# Sedna_Power_Board_v3.net
KiCad netlist of a schematic drawn in EAGLE
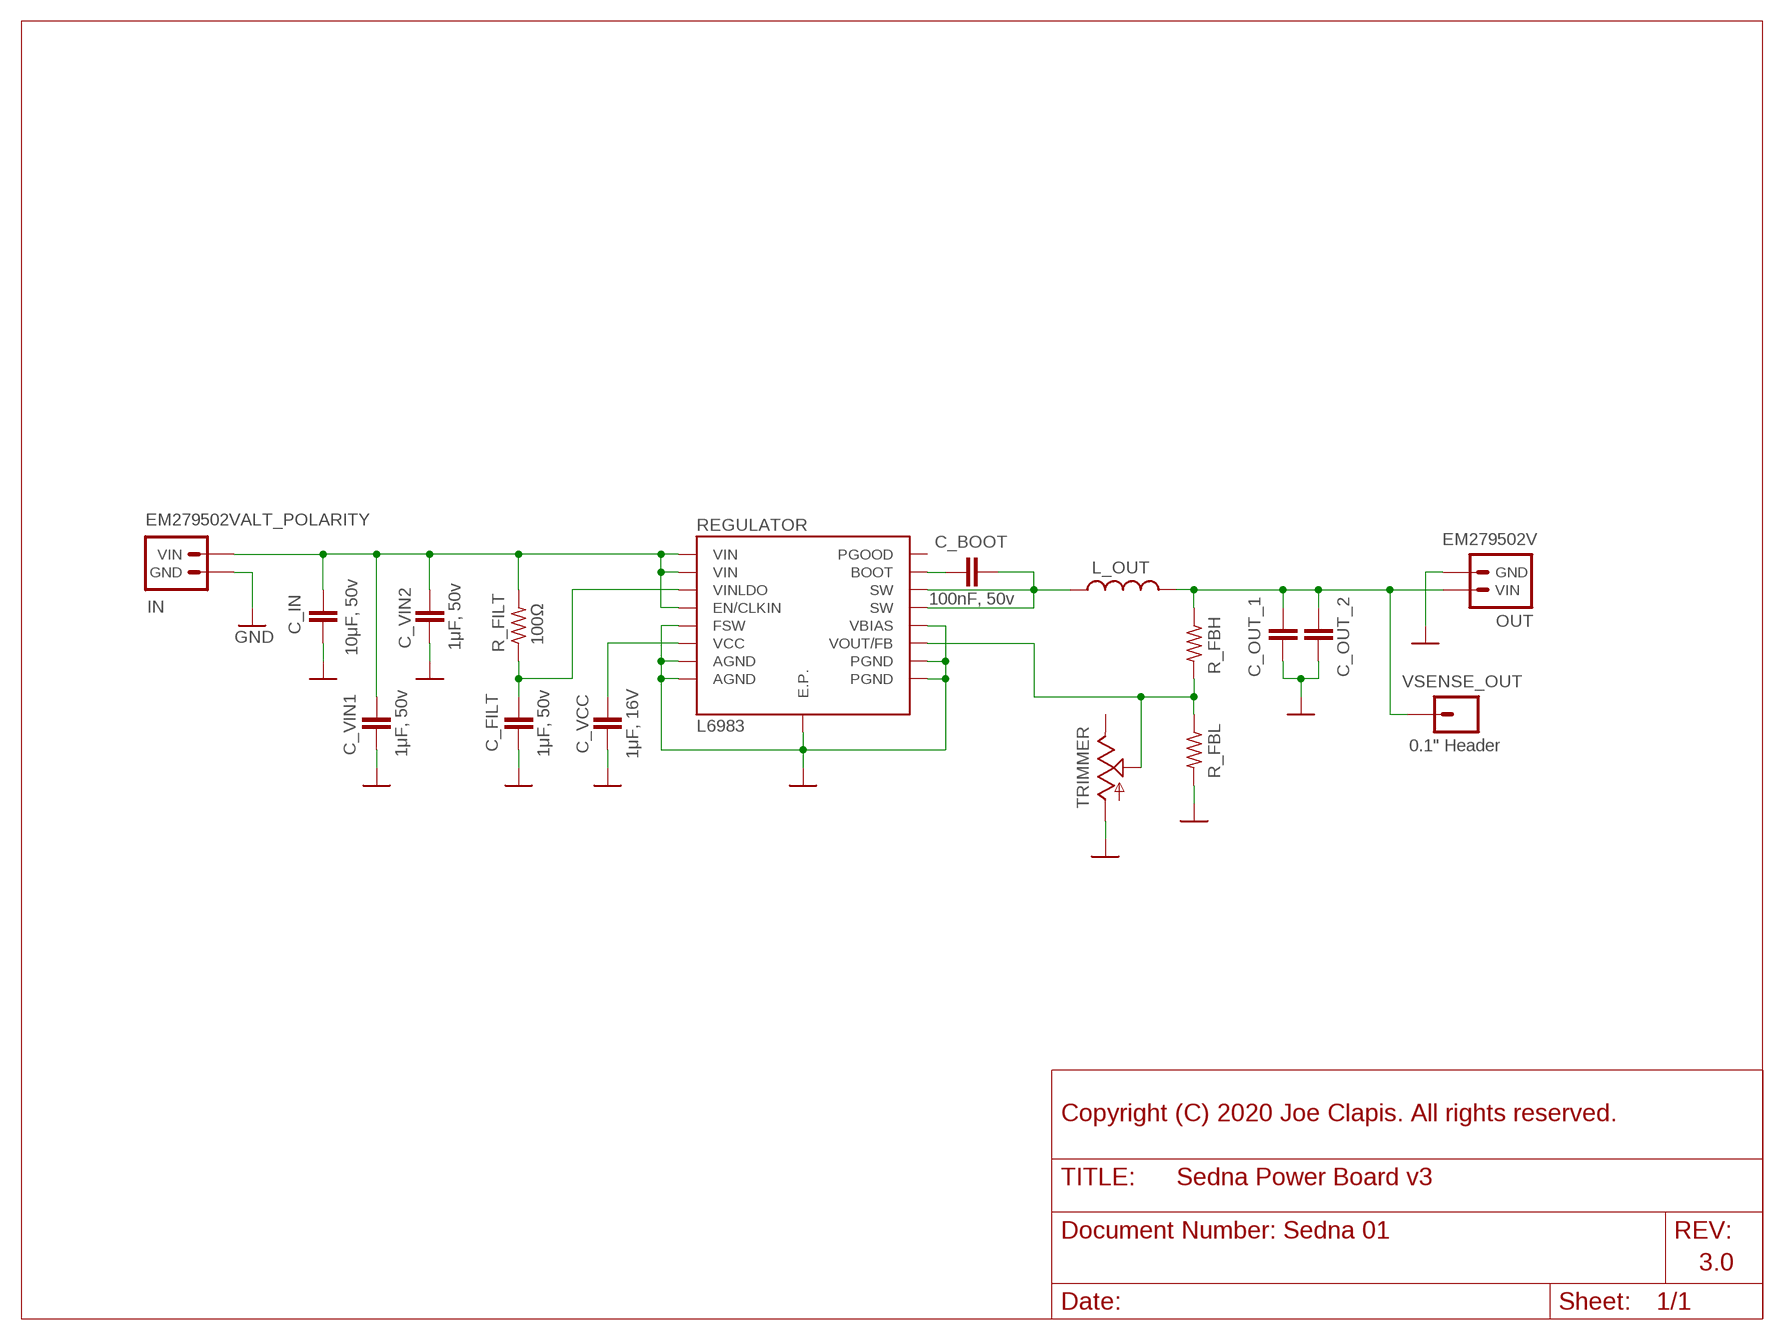
[diagram p0: schematic, sheet 1]

(export (version "E")
  (design (tool "Eeschema 10.0.6"))
  (components
    (comp (ref "C_BOOT")
      (value "100nF, 50v")
      (footprint "eagle-import:C0805")
      (libsource (lib "eagle-import") (part "C-EUC0805"))
    )
    (comp (ref "C_FILT")
      (value "1μF, 50v")
      (footprint "eagle-import:C0805")
      (libsource (lib "eagle-import") (part "C-EUC0805"))
    )
    (comp (ref "C_IN")
      (value "10μF, 50v")
      (footprint "eagle-import:C1206")
      (libsource (lib "eagle-import") (part "C-EUC1206"))
    )
    (comp (ref "C_OUT_1")
      (value "TDK_C2220_5750")
      (footprint "eagle-import:TDK_C2220_5750")
      (libsource (lib "eagle-import") (part "TDK_C2220_5750"))
    )
    (comp (ref "C_OUT_2")
      (value "TDK_C2220_5750")
      (footprint "eagle-import:TDK_C2220_5750")
      (libsource (lib "eagle-import") (part "TDK_C2220_5750"))
    )
    (comp (ref "C_VCC")
      (value "1μF, 16V")
      (footprint "eagle-import:C0805")
      (libsource (lib "eagle-import") (part "C-EUC0805"))
    )
    (comp (ref "C_VIN1")
      (value "1μF, 50v")
      (footprint "eagle-import:C0805")
      (libsource (lib "eagle-import") (part "C-EUC0805"))
    )
    (comp (ref "C_VIN2")
      (value "1μF, 50v")
      (footprint "eagle-import:C0805")
      (libsource (lib "eagle-import") (part "C-EUC0805"))
    )
    (comp (ref "IN")
      (value "EM279502VALT_POLARITY")
      (footprint "eagle-import:EM279502V")
      (libsource (lib "eagle-import") (part "EM279502VALT_POLARITY"))
    )
    (comp (ref "L_OUT")
      (value "PA4343_FP2")
      (footprint "eagle-import:PA4343_FP2")
      (libsource (lib "eagle-import") (part "PA4343_FP2"))
    )
    (comp (ref "OUT")
      (value "EM279502V")
      (footprint "eagle-import:EM279502V")
      (libsource (lib "eagle-import") (part "EM279502V"))
    )
    (comp (ref "REGULATOR")
      (value "L6983")
      (footprint "eagle-import:L6983")
      (fields (field (name "SPICEPREFIX") "X"))
      (libsource (lib "eagle-import") (part "L6983"))
    )
    (comp (ref "R_FBH")
      (value "R-US_R0805")
      (footprint "eagle-import:R0805")
      (libsource (lib "eagle-import") (part "R-US_R0805"))
    )
    (comp (ref "R_FBL")
      (value "R-US_R0805")
      (footprint "eagle-import:R0805")
      (libsource (lib "eagle-import") (part "R-US_R0805"))
    )
    (comp (ref "R_FILT")
      (value "100Ω")
      (footprint "eagle-import:R0805")
      (libsource (lib "eagle-import") (part "R-US_R0805"))
    )
    (comp (ref "TRIMMER")
      (value "BOURNS_3361S")
      (footprint "eagle-import:BOURNS_3361S")
      (libsource (lib "eagle-import") (part "BOURNS_3361S"))
    )
    (comp (ref "VSENSE_OUT")
      (value "0.1\" Header")
      (footprint "eagle-import:1X01")
      (libsource (lib "eagle-import") (part "M01PTH"))
    )
  )
  (nets
    (net (code "1") (name "GND") (class "Default")
      (node (ref "C_FILT") (pin "2") (pinfunction "2_2") (pintype "passive"))
      (node (ref "C_IN") (pin "2") (pinfunction "2_2") (pintype "passive"))
      (node (ref "C_OUT_1") (pin "2") (pinfunction "2_2") (pintype "passive"))
      (node (ref "C_OUT_2") (pin "2") (pinfunction "2_2") (pintype "passive"))
      (node (ref "C_VCC") (pin "2") (pinfunction "2_2") (pintype "passive"))
      (node (ref "C_VIN1") (pin "2") (pinfunction "2_2") (pintype "passive"))
      (node (ref "C_VIN2") (pin "2") (pinfunction "2_2") (pintype "passive"))
      (node (ref "IN") (pin "1A") (pinfunction "GND_1A") (pintype "passive"))
      (node (ref "IN") (pin "1B") (pinfunction "GND_1B") (pintype "passive"))
      (node (ref "OUT") (pin "2A") (pinfunction "GND_2A") (pintype "passive"))
      (node (ref "OUT") (pin "2B") (pinfunction "GND_2B") (pintype "passive"))
      (node (ref "REGULATOR") (pin "10_AGND") (pinfunction "AGND_10_AGND") (pintype "power_in"))
      (node (ref "REGULATOR") (pin "13_PGND") (pinfunction "PGND_13_PGND") (pintype "power_in"))
      (node (ref "REGULATOR") (pin "16_PGND") (pinfunction "PGND_16_PGND") (pintype "power_in"))
      (node (ref "REGULATOR") (pin "3_AGND") (pinfunction "AGND_3_AGND") (pintype "power_in"))
      (node (ref "REGULATOR") (pin "6_VBIAS") (pinfunction "VBIAS_6_VBIAS") (pintype "input"))
      (node (ref "REGULATOR") (pin "8_FSW") (pinfunction "FSW_8_FSW") (pintype "output"))
      (node (ref "REGULATOR") (pin "E.P.") (pinfunction "E.P._E.P.") (pintype "power_in"))
      (node (ref "R_FBL") (pin "2") (pinfunction "2_2") (pintype "passive"))
      (node (ref "TRIMMER") (pin "1") (pinfunction "A_1") (pintype "passive"))
    )
    (net (code "2") (name "Net-(C_BOOT-Pad2)") (class "Default")
      (node (ref "C_BOOT") (pin "2") (pinfunction "2_2") (pintype "passive"))
      (node (ref "L_OUT") (pin "1") (pinfunction "1_1") (pintype "passive"))
      (node (ref "REGULATOR") (pin "14_SW") (pinfunction "SW_14_SW") (pintype "power_in"))
      (node (ref "REGULATOR") (pin "15_SW") (pinfunction "SW_15_SW") (pintype "power_in"))
    )
    (net (code "3") (name "Net-(C_OUT_1-Pad1)") (class "Default")
      (node (ref "C_OUT_1") (pin "1") (pinfunction "1_1") (pintype "passive"))
      (node (ref "C_OUT_2") (pin "1") (pinfunction "1_1") (pintype "passive"))
      (node (ref "L_OUT") (pin "2") (pinfunction "2_2") (pintype "passive"))
      (node (ref "OUT") (pin "1A") (pinfunction "VIN_1A") (pintype "passive"))
      (node (ref "OUT") (pin "1B") (pinfunction "VIN_1B") (pintype "passive"))
      (node (ref "R_FBH") (pin "1") (pinfunction "1_1") (pintype "passive"))
      (node (ref "VSENSE_OUT") (pin "1") (pinfunction "1_1") (pintype "passive"))
    )
    (net (code "4") (name "Net-(REGULATOR-BOOT)") (class "Default")
      (node (ref "C_BOOT") (pin "1") (pinfunction "1_1") (pintype "passive"))
      (node (ref "REGULATOR") (pin "11_BOOT") (pinfunction "BOOT_11_BOOT") (pintype "power_in"))
    )
    (net (code "5") (name "Net-(REGULATOR-EN{slash}CLKIN)") (class "Default")
      (node (ref "C_IN") (pin "1") (pinfunction "1_1") (pintype "passive"))
      (node (ref "C_VIN1") (pin "1") (pinfunction "1_1") (pintype "passive"))
      (node (ref "C_VIN2") (pin "1") (pinfunction "1_1") (pintype "passive"))
      (node (ref "IN") (pin "2A") (pinfunction "VIN_2A") (pintype "passive"))
      (node (ref "IN") (pin "2B") (pinfunction "VIN_2B") (pintype "passive"))
      (node (ref "REGULATOR") (pin "12_VIN") (pinfunction "VIN_12_VIN") (pintype "power_in"))
      (node (ref "REGULATOR") (pin "1_VIN") (pinfunction "VIN_1_VIN") (pintype "power_in"))
      (node (ref "REGULATOR") (pin "4_EN/CLKIN") (pinfunction "EN/CLKIN_4_EN/CLKIN") (pintype "input"))
      (node (ref "R_FILT") (pin "2") (pinfunction "2_2") (pintype "passive"))
    )
    (net (code "6") (name "Net-(REGULATOR-VCC)") (class "Default")
      (node (ref "C_VCC") (pin "1") (pinfunction "1_1") (pintype "passive"))
      (node (ref "REGULATOR") (pin "9_VCC") (pinfunction "VCC_9_VCC") (pintype "power_in"))
    )
    (net (code "7") (name "Net-(REGULATOR-VINLDO)") (class "Default")
      (node (ref "C_FILT") (pin "1") (pinfunction "1_1") (pintype "passive"))
      (node (ref "REGULATOR") (pin "2_VINLDO") (pinfunction "VINLDO_2_VINLDO") (pintype "power_in"))
      (node (ref "R_FILT") (pin "1") (pinfunction "1_1") (pintype "passive"))
    )
    (net (code "8") (name "Net-(REGULATOR-VOUT{slash}FB)") (class "Default")
      (node (ref "REGULATOR") (pin "7_FB/VOUT") (pinfunction "VOUT/FB_7_FB/VOUT") (pintype "input"))
      (node (ref "R_FBH") (pin "2") (pinfunction "2_2") (pintype "passive"))
      (node (ref "R_FBL") (pin "1") (pinfunction "1_1") (pintype "passive"))
      (node (ref "TRIMMER") (pin "2") (pinfunction "S_2") (pintype "passive"))
    )
    (net (code "9") (name "unconnected-(REGULATOR-PGOOD-Pad5_PGOOD)") (class "Default")
      (node (ref "REGULATOR") (pin "5_PGOOD") (pinfunction "PGOOD_5_PGOOD") (pintype "output"))
    )
    (net (code "10") (name "unconnected-(TRIMMER-E-Pad3)") (class "Default")
      (node (ref "TRIMMER") (pin "3") (pinfunction "E_3") (pintype "passive"))
    )
  )
)
